# rp3a0-mini-gpio.net
KiCad netlist of a schematic drawn in Altium Designer
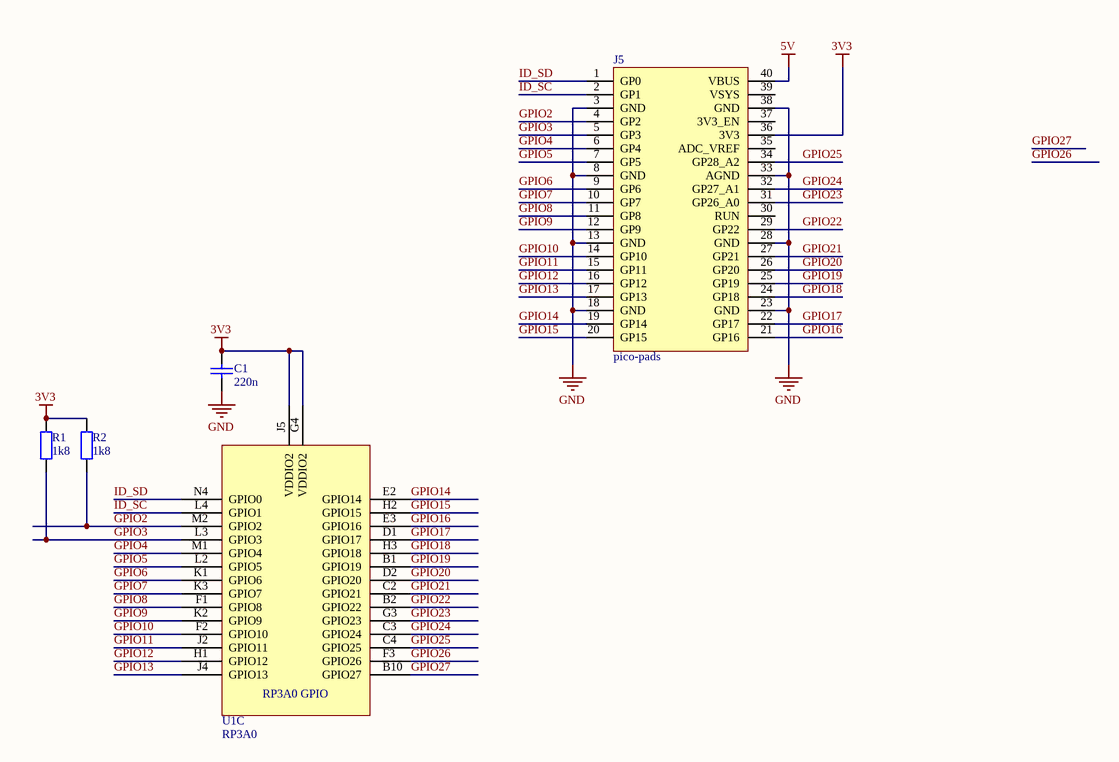
[diagram p0: rp3a0-mini-gpio.SchDoc]

(export (version "E")
  (design (tool "Eeschema 10.0.6"))
  (components
    (comp (ref "C1")
      (value "220n")
      (footprint "0402")
      (description "Capacitor")
      (fields (field (name "Comment") "Cap"))
      (libsource (lib "custom-lib") (part "CAP-NONPOL"))
    )
    (comp (ref "J5") (value "pico-pads") (footprint "PICO_PADS") (libsource (lib "rp3a0") (part "pico-pads")))
    (comp (ref "R1")
      (value "1k8")
      (footprint "RES-0402-SML")
      (description "Resistor")
      (fields (field (name "Comment") "Res SMD"))
      (libsource (lib "custom-lib") (part "Res SMD"))
    )
    (comp (ref "R2")
      (value "1k8")
      (footprint "RES-0402-SML")
      (description "Resistor")
      (fields (field (name "Comment") "Res SMD"))
      (libsource (lib "custom-lib") (part "Res SMD"))
    )
    (comp (ref "U1") (value "RP3A0") (footprint "RP3A0-BGA") (libsource (lib "rp3a0") (part "RP3A0")))
  )
  (nets
    (net (code "1") (name "/GPIO2") (class "Default")
      (node (ref "J5") (pin "4") (pinfunction "GP2_4") (pintype "passive"))
      (node (ref "R2") (pin "1") (pinfunction "1_1") (pintype "passive"))
      (node (ref "U1") (pin "M2") (pinfunction "GPIO2_M2") (pintype "passive"))
    )
    (net (code "2") (name "/GPIO3") (class "Default")
      (node (ref "J5") (pin "5") (pinfunction "GP3_5") (pintype "passive"))
      (node (ref "R1") (pin "1") (pinfunction "1_1") (pintype "passive"))
      (node (ref "U1") (pin "L3") (pinfunction "GPIO3_L3") (pintype "passive"))
    )
    (net (code "3") (name "/GPIO4") (class "Default")
      (node (ref "J5") (pin "6") (pinfunction "GP4_6") (pintype "passive"))
      (node (ref "U1") (pin "M1") (pinfunction "GPIO4_M1") (pintype "passive"))
    )
    (net (code "4") (name "/GPIO5") (class "Default")
      (node (ref "J5") (pin "7") (pinfunction "GP5_7") (pintype "passive"))
      (node (ref "U1") (pin "L2") (pinfunction "GPIO5_L2") (pintype "passive"))
    )
    (net (code "5") (name "/GPIO6") (class "Default")
      (node (ref "J5") (pin "9") (pinfunction "GP6_9") (pintype "passive"))
      (node (ref "U1") (pin "K1") (pinfunction "GPIO6_K1") (pintype "passive"))
    )
    (net (code "6") (name "/GPIO7") (class "Default")
      (node (ref "J5") (pin "10") (pinfunction "GP7_10") (pintype "passive"))
      (node (ref "U1") (pin "K3") (pinfunction "GPIO7_K3") (pintype "passive"))
    )
    (net (code "7") (name "/GPIO8") (class "Default")
      (node (ref "J5") (pin "11") (pinfunction "GP8_11") (pintype "passive"))
      (node (ref "U1") (pin "F1") (pinfunction "GPIO8_F1") (pintype "passive"))
    )
    (net (code "8") (name "/GPIO9") (class "Default")
      (node (ref "J5") (pin "12") (pinfunction "GP9_12") (pintype "passive"))
      (node (ref "U1") (pin "K2") (pinfunction "GPIO9_K2") (pintype "passive"))
    )
    (net (code "9") (name "/GPIO10") (class "Default")
      (node (ref "J5") (pin "14") (pinfunction "GP10_14") (pintype "passive"))
      (node (ref "U1") (pin "F2") (pinfunction "GPIO10_F2") (pintype "passive"))
    )
    (net (code "10") (name "/GPIO11") (class "Default")
      (node (ref "J5") (pin "15") (pinfunction "GP11_15") (pintype "passive"))
      (node (ref "U1") (pin "J2") (pinfunction "GPIO11_J2") (pintype "passive"))
    )
    (net (code "11") (name "/GPIO12") (class "Default")
      (node (ref "J5") (pin "16") (pinfunction "GP12_16") (pintype "passive"))
      (node (ref "U1") (pin "H1") (pinfunction "GPIO12_H1") (pintype "passive"))
    )
    (net (code "12") (name "/GPIO13") (class "Default")
      (node (ref "J5") (pin "17") (pinfunction "GP13_17") (pintype "passive"))
      (node (ref "U1") (pin "J4") (pinfunction "GPIO13_J4") (pintype "passive"))
    )
    (net (code "13") (name "/GPIO14") (class "Default")
      (node (ref "J5") (pin "19") (pinfunction "GP14_19") (pintype "passive"))
      (node (ref "U1") (pin "E2") (pinfunction "GPIO14_E2") (pintype "passive"))
    )
    (net (code "14") (name "/GPIO15") (class "Default")
      (node (ref "J5") (pin "20") (pinfunction "GP15_20") (pintype "passive"))
      (node (ref "U1") (pin "H2") (pinfunction "GPIO15_H2") (pintype "passive"))
    )
    (net (code "15") (name "/GPIO16") (class "Default")
      (node (ref "J5") (pin "21") (pinfunction "GP16_21") (pintype "passive"))
      (node (ref "U1") (pin "E3") (pinfunction "GPIO16_E3") (pintype "passive"))
    )
    (net (code "16") (name "/GPIO17") (class "Default")
      (node (ref "J5") (pin "22") (pinfunction "GP17_22") (pintype "passive"))
      (node (ref "U1") (pin "D1") (pinfunction "GPIO17_D1") (pintype "passive"))
    )
    (net (code "17") (name "/GPIO18") (class "Default")
      (node (ref "J5") (pin "24") (pinfunction "GP18_24") (pintype "passive"))
      (node (ref "U1") (pin "H3") (pinfunction "GPIO18_H3") (pintype "passive"))
    )
    (net (code "18") (name "/GPIO19") (class "Default")
      (node (ref "J5") (pin "25") (pinfunction "GP19_25") (pintype "passive"))
      (node (ref "U1") (pin "B1") (pinfunction "GPIO19_B1") (pintype "passive"))
    )
    (net (code "19") (name "/GPIO20") (class "Default")
      (node (ref "J5") (pin "26") (pinfunction "GP20_26") (pintype "passive"))
      (node (ref "U1") (pin "D2") (pinfunction "GPIO20_D2") (pintype "passive"))
    )
    (net (code "20") (name "/GPIO21") (class "Default")
      (node (ref "J5") (pin "27") (pinfunction "GP21_27") (pintype "passive"))
      (node (ref "U1") (pin "C2") (pinfunction "GPIO21_C2") (pintype "passive"))
    )
    (net (code "21") (name "/GPIO22") (class "Default")
      (node (ref "J5") (pin "29") (pinfunction "GP22_29") (pintype "passive"))
      (node (ref "U1") (pin "B2") (pinfunction "GPIO22_B2") (pintype "passive"))
    )
    (net (code "22") (name "/GPIO23") (class "Default")
      (node (ref "J5") (pin "31") (pinfunction "GP26_A0_31") (pintype "passive"))
      (node (ref "U1") (pin "G3") (pinfunction "GPIO23_G3") (pintype "passive"))
    )
    (net (code "23") (name "/GPIO24") (class "Default")
      (node (ref "J5") (pin "32") (pinfunction "GP27_A1_32") (pintype "passive"))
      (node (ref "U1") (pin "C3") (pinfunction "GPIO24_C3") (pintype "passive"))
    )
    (net (code "24") (name "/GPIO25") (class "Default")
      (node (ref "J5") (pin "34") (pinfunction "GP28_A2_34") (pintype "passive"))
      (node (ref "U1") (pin "C4") (pinfunction "GPIO25_C4") (pintype "passive"))
    )
    (net (code "25") (name "/GPIO26") (class "Default")
      (node (ref "U1") (pin "F3") (pinfunction "GPIO26_F3") (pintype "passive"))
    )
    (net (code "26") (name "/GPIO27") (class "Default")
      (node (ref "U1") (pin "B10") (pinfunction "GPIO27_B10") (pintype "passive"))
    )
    (net (code "27") (name "/ID_SC") (class "Default")
      (node (ref "J5") (pin "2") (pinfunction "GP1_2") (pintype "passive"))
      (node (ref "U1") (pin "L4") (pinfunction "GPIO1_L4") (pintype "passive"))
    )
    (net (code "28") (name "/ID_SD") (class "Default")
      (node (ref "J5") (pin "1") (pinfunction "GP0_1") (pintype "passive"))
      (node (ref "U1") (pin "N4") (pinfunction "GPIO0_N4") (pintype "passive"))
    )
    (net (code "29") (name "3V3") (class "Default")
      (node (ref "C1") (pin "2") (pinfunction "2_2") (pintype "passive"))
      (node (ref "J5") (pin "36") (pinfunction "3V3_36") (pintype "passive"))
      (node (ref "R1") (pin "2") (pinfunction "2_2") (pintype "passive"))
      (node (ref "R2") (pin "2") (pinfunction "2_2") (pintype "passive"))
      (node (ref "U1") (pin "G4") (pinfunction "VDDIO2_G4") (pintype "passive"))
      (node (ref "U1") (pin "J5") (pinfunction "VDDIO2_J5") (pintype "passive"))
    )
    (net (code "30") (name "5V") (class "Default")
      (node (ref "J5") (pin "40") (pinfunction "VBUS_40") (pintype "passive"))
    )
    (net (code "31") (name "GND") (class "Default")
      (node (ref "C1") (pin "1") (pinfunction "1_1") (pintype "passive"))
      (node (ref "J5") (pin "13") (pinfunction "GND_13") (pintype "passive"))
      (node (ref "J5") (pin "18") (pinfunction "GND_18") (pintype "passive"))
      (node (ref "J5") (pin "23") (pinfunction "GND_23") (pintype "passive"))
      (node (ref "J5") (pin "28") (pinfunction "GND_28") (pintype "passive"))
      (node (ref "J5") (pin "3") (pinfunction "GND_3") (pintype "passive"))
      (node (ref "J5") (pin "33") (pinfunction "AGND_33") (pintype "passive"))
      (node (ref "J5") (pin "38") (pinfunction "GND_38") (pintype "passive"))
      (node (ref "J5") (pin "8") (pinfunction "GND_8") (pintype "passive"))
    )
    (net (code "32") (name "unconnected-(J5-3V3_EN-Pad37)") (class "Default")
      (node (ref "J5") (pin "37") (pinfunction "3V3_EN_37") (pintype "passive"))
    )
    (net (code "33") (name "unconnected-(J5-ADC_VREF-Pad35)") (class "Default")
      (node (ref "J5") (pin "35") (pinfunction "ADC_VREF_35") (pintype "passive"))
    )
    (net (code "34") (name "unconnected-(J5-RUN-Pad30)") (class "Default")
      (node (ref "J5") (pin "30") (pinfunction "RUN_30") (pintype "passive"))
    )
    (net (code "35") (name "unconnected-(J5-VSYS-Pad39)") (class "Default")
      (node (ref "J5") (pin "39") (pinfunction "VSYS_39") (pintype "passive"))
    )
  )
)
